# NXPESC-UF1_test004.net
KiCad netlist of a schematic drawn in EAGLE
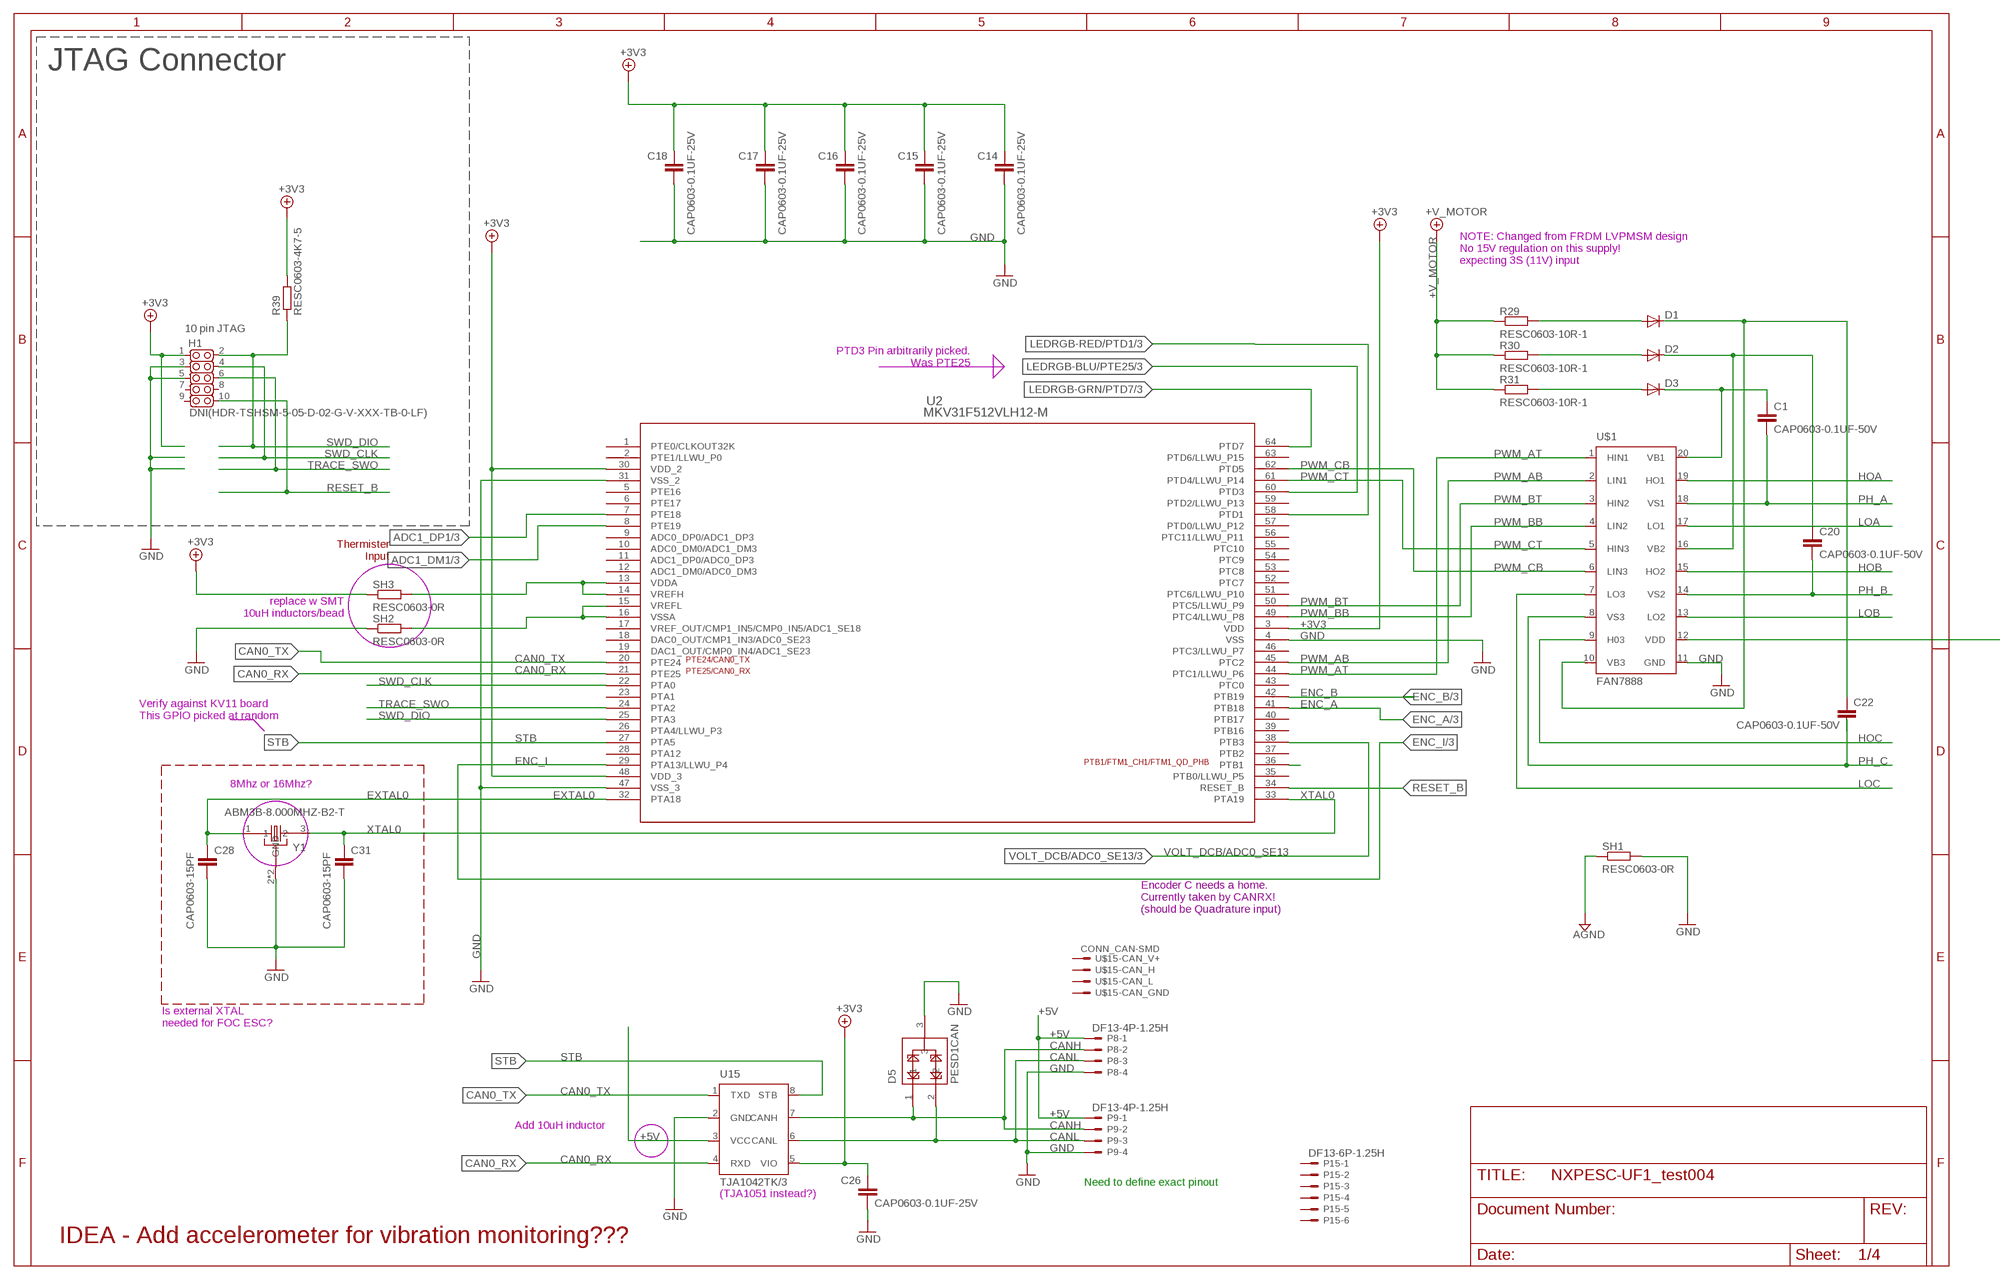
[diagram p0: schematic, sheet 1, part 1 of 2]
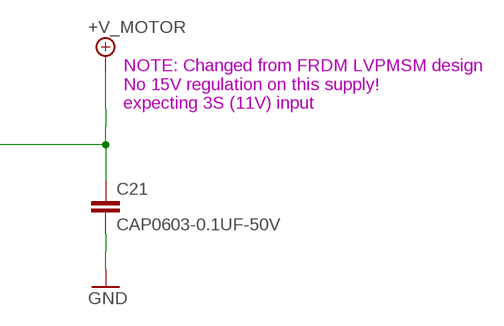
[diagram p1: schematic, sheet 1, part 2 of 2]
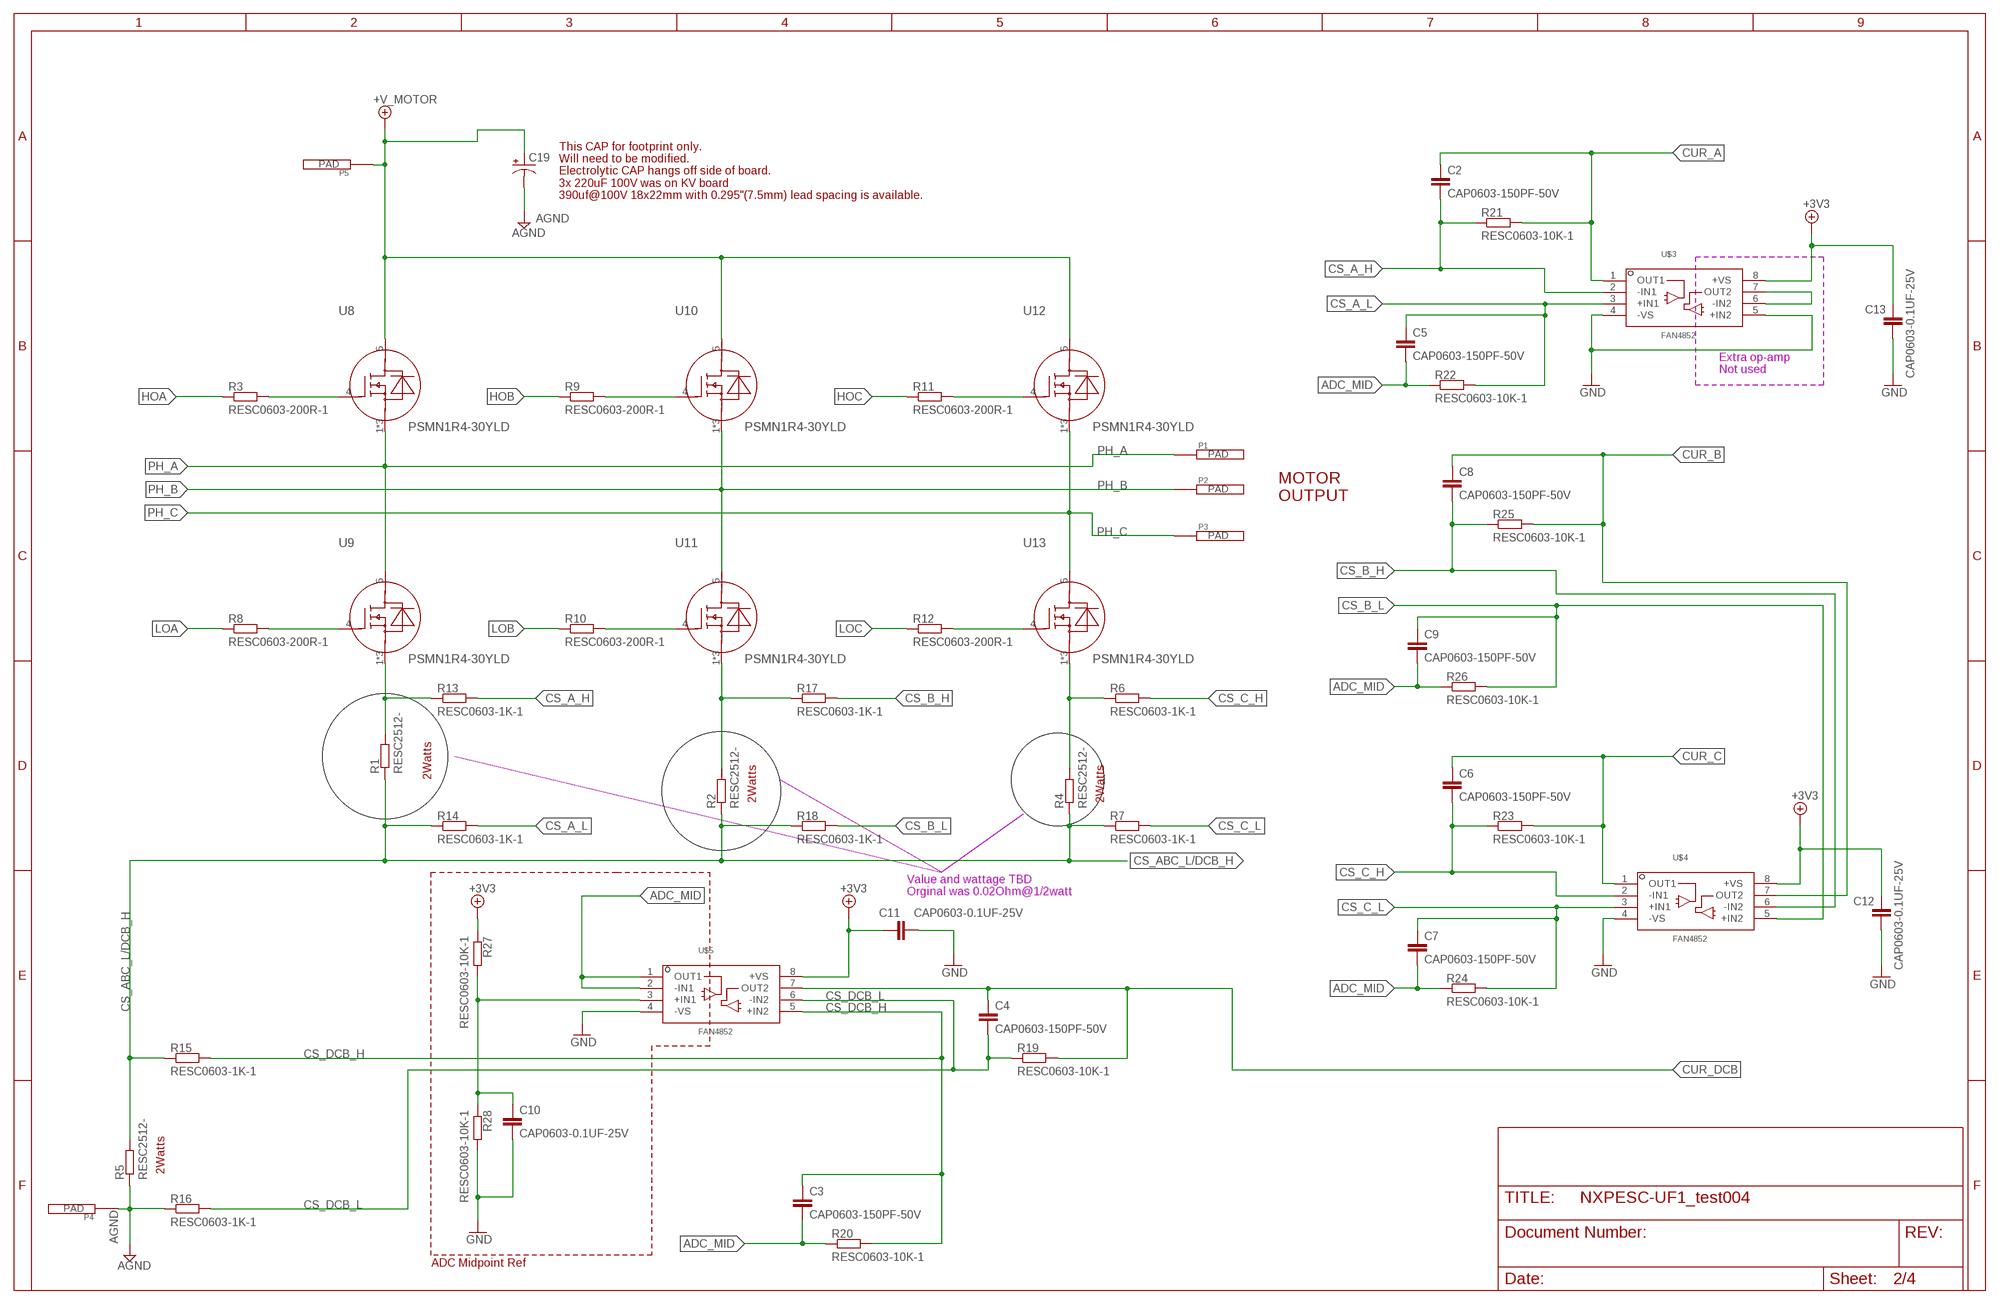
[diagram p2: schematic, sheet 2]
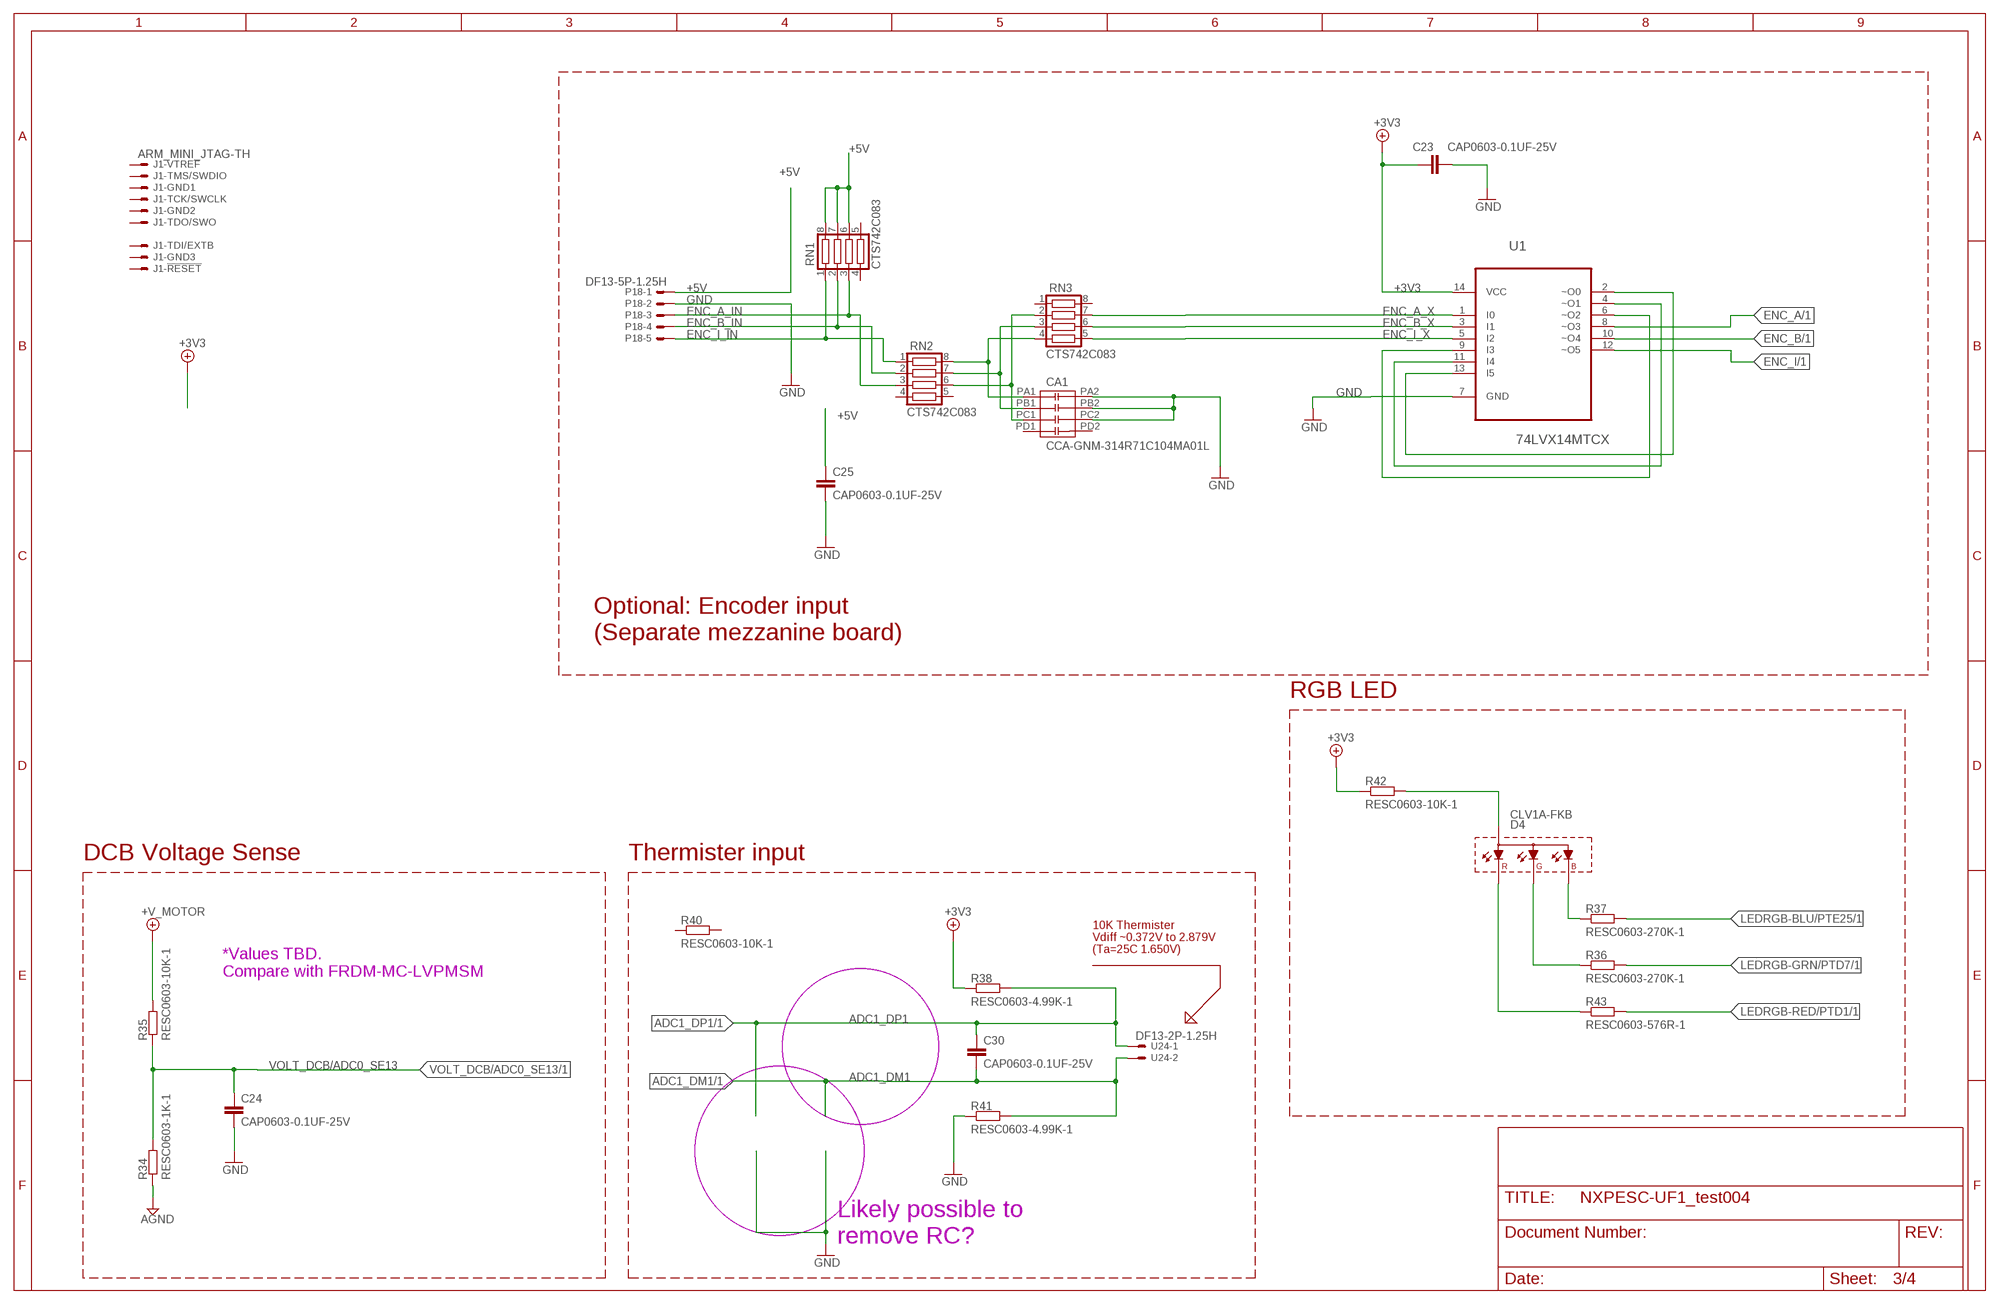
[diagram p3: schematic, sheet 3]

(export (version "E")
  (design (tool "Eeschema 10.0.6"))
  (components
    (comp (ref "C2")
      (value "CAP0603-150PF-50V")
      (footprint "eagle-import:C0603")
      (libsource (lib "eagle-import") (part "CAP?-0603150PF-50V"))
    )
    (comp (ref "C3")
      (value "CAP0603-150PF-50V")
      (footprint "eagle-import:C0603")
      (libsource (lib "eagle-import") (part "CAP?-0603150PF-50V"))
    )
    (comp (ref "C4")
      (value "CAP0603-150PF-50V")
      (footprint "eagle-import:C0603")
      (libsource (lib "eagle-import") (part "CAP?-0603150PF-50V"))
    )
    (comp (ref "C5")
      (value "CAP0603-150PF-50V")
      (footprint "eagle-import:C0603")
      (libsource (lib "eagle-import") (part "CAP?-0603150PF-50V"))
    )
    (comp (ref "C6")
      (value "CAP0603-150PF-50V")
      (footprint "eagle-import:C0603")
      (libsource (lib "eagle-import") (part "CAP?-0603150PF-50V"))
    )
    (comp (ref "C7")
      (value "CAP0603-150PF-50V")
      (footprint "eagle-import:C0603")
      (libsource (lib "eagle-import") (part "CAP?-0603150PF-50V"))
    )
    (comp (ref "C8")
      (value "CAP0603-150PF-50V")
      (footprint "eagle-import:C0603")
      (libsource (lib "eagle-import") (part "CAP?-0603150PF-50V"))
    )
    (comp (ref "C9")
      (value "CAP0603-150PF-50V")
      (footprint "eagle-import:C0603")
      (libsource (lib "eagle-import") (part "CAP?-0603150PF-50V"))
    )
    (comp (ref "C10")
      (value "CAP0603-0.1UF-25V")
      (footprint "eagle-import:C0603")
      (libsource (lib "eagle-import") (part "CAP?-06030.1UF-25V"))
    )
    (comp (ref "C11")
      (value "CAP0603-0.1UF-25V")
      (footprint "eagle-import:C0603")
      (libsource (lib "eagle-import") (part "CAP?-06030.1UF-25V"))
    )
    (comp (ref "C12")
      (value "CAP0603-0.1UF-25V")
      (footprint "eagle-import:C0603")
      (libsource (lib "eagle-import") (part "CAP?-06030.1UF-25V"))
    )
    (comp (ref "C13")
      (value "CAP0603-0.1UF-25V")
      (footprint "eagle-import:C0603")
      (libsource (lib "eagle-import") (part "CAP?-06030.1UF-25V"))
    )
    (comp (ref "C19")
      (value "CPOL-USETR1")
      (footprint "eagle-import:ETR1")
      (libsource (lib "eagle-import") (part "CPOL-USETR1"))
    )
    (comp (ref "P1")
      (value "MOT_PWR_PAD-1")
      (footprint "eagle-import:MPAD1")
      (libsource (lib "eagle-import") (part "MOT_PWR_PAD-1"))
    )
    (comp (ref "P2")
      (value "MOT_PWR_PAD-1")
      (footprint "eagle-import:MPAD1")
      (libsource (lib "eagle-import") (part "MOT_PWR_PAD-1"))
    )
    (comp (ref "P3")
      (value "MOT_PWR_PAD-1")
      (footprint "eagle-import:MPAD1")
      (libsource (lib "eagle-import") (part "MOT_PWR_PAD-1"))
    )
    (comp (ref "P4")
      (value "MOT_PWR_PAD-1")
      (footprint "eagle-import:MPAD1")
      (libsource (lib "eagle-import") (part "MOT_PWR_PAD-1"))
    )
    (comp (ref "P5")
      (value "MOT_PWR_PAD-1")
      (footprint "eagle-import:MPAD1")
      (libsource (lib "eagle-import") (part "MOT_PWR_PAD-1"))
    )
    (comp (ref "R1")
      (value "RESC2512-")
      (footprint "eagle-import:R2512")
      (libsource (lib "eagle-import") (part "RESC?-2512"))
    )
    (comp (ref "R2")
      (value "RESC2512-")
      (footprint "eagle-import:R2512")
      (libsource (lib "eagle-import") (part "RESC?-2512"))
    )
    (comp (ref "R3")
      (value "RESC0603-200R-1")
      (footprint "eagle-import:C0603")
      (libsource (lib "eagle-import") (part "RESC?-0603200R-1"))
    )
    (comp (ref "R4")
      (value "RESC2512-")
      (footprint "eagle-import:R2512")
      (libsource (lib "eagle-import") (part "RESC?-2512"))
    )
    (comp (ref "R5")
      (value "RESC2512-")
      (footprint "eagle-import:R2512")
      (libsource (lib "eagle-import") (part "RESC?-2512"))
    )
    (comp (ref "R6")
      (value "RESC0603-1K-1")
      (footprint "eagle-import:C0603")
      (libsource (lib "eagle-import") (part "RESC?-06031K-1"))
    )
    (comp (ref "R7")
      (value "RESC0603-1K-1")
      (footprint "eagle-import:C0603")
      (libsource (lib "eagle-import") (part "RESC?-06031K-1"))
    )
    (comp (ref "R8")
      (value "RESC0603-200R-1")
      (footprint "eagle-import:C0603")
      (libsource (lib "eagle-import") (part "RESC?-0603200R-1"))
    )
    (comp (ref "R9")
      (value "RESC0603-200R-1")
      (footprint "eagle-import:C0603")
      (libsource (lib "eagle-import") (part "RESC?-0603200R-1"))
    )
    (comp (ref "R10")
      (value "RESC0603-200R-1")
      (footprint "eagle-import:C0603")
      (libsource (lib "eagle-import") (part "RESC?-0603200R-1"))
    )
    (comp (ref "R11")
      (value "RESC0603-200R-1")
      (footprint "eagle-import:C0603")
      (libsource (lib "eagle-import") (part "RESC?-0603200R-1"))
    )
    (comp (ref "R12")
      (value "RESC0603-200R-1")
      (footprint "eagle-import:C0603")
      (libsource (lib "eagle-import") (part "RESC?-0603200R-1"))
    )
    (comp (ref "R13")
      (value "RESC0603-1K-1")
      (footprint "eagle-import:C0603")
      (libsource (lib "eagle-import") (part "RESC?-06031K-1"))
    )
    (comp (ref "R14")
      (value "RESC0603-1K-1")
      (footprint "eagle-import:C0603")
      (libsource (lib "eagle-import") (part "RESC?-06031K-1"))
    )
    (comp (ref "R15")
      (value "RESC0603-1K-1")
      (footprint "eagle-import:C0603")
      (libsource (lib "eagle-import") (part "RESC?-06031K-1"))
    )
    (comp (ref "R16")
      (value "RESC0603-1K-1")
      (footprint "eagle-import:C0603")
      (libsource (lib "eagle-import") (part "RESC?-06031K-1"))
    )
    (comp (ref "R17")
      (value "RESC0603-1K-1")
      (footprint "eagle-import:C0603")
      (libsource (lib "eagle-import") (part "RESC?-06031K-1"))
    )
    (comp (ref "R18")
      (value "RESC0603-1K-1")
      (footprint "eagle-import:C0603")
      (libsource (lib "eagle-import") (part "RESC?-06031K-1"))
    )
    (comp (ref "R19")
      (value "RESC0603-10K-1")
      (footprint "eagle-import:C0603")
      (libsource (lib "eagle-import") (part "RESC?-060310K-1"))
    )
    (comp (ref "R20")
      (value "RESC0603-10K-1")
      (footprint "eagle-import:C0603")
      (libsource (lib "eagle-import") (part "RESC?-060310K-1"))
    )
    (comp (ref "R21")
      (value "RESC0603-10K-1")
      (footprint "eagle-import:C0603")
      (libsource (lib "eagle-import") (part "RESC?-060310K-1"))
    )
    (comp (ref "R22")
      (value "RESC0603-10K-1")
      (footprint "eagle-import:C0603")
      (libsource (lib "eagle-import") (part "RESC?-060310K-1"))
    )
    (comp (ref "R23")
      (value "RESC0603-10K-1")
      (footprint "eagle-import:C0603")
      (libsource (lib "eagle-import") (part "RESC?-060310K-1"))
    )
    (comp (ref "R24")
      (value "RESC0603-10K-1")
      (footprint "eagle-import:C0603")
      (libsource (lib "eagle-import") (part "RESC?-060310K-1"))
    )
    (comp (ref "R25")
      (value "RESC0603-10K-1")
      (footprint "eagle-import:C0603")
      (libsource (lib "eagle-import") (part "RESC?-060310K-1"))
    )
    (comp (ref "R26")
      (value "RESC0603-10K-1")
      (footprint "eagle-import:C0603")
      (libsource (lib "eagle-import") (part "RESC?-060310K-1"))
    )
    (comp (ref "R27")
      (value "RESC0603-10K-1")
      (footprint "eagle-import:C0603")
      (libsource (lib "eagle-import") (part "RESC?-060310K-1"))
    )
    (comp (ref "R28")
      (value "RESC0603-10K-1")
      (footprint "eagle-import:C0603")
      (libsource (lib "eagle-import") (part "RESC?-060310K-1"))
    )
    (comp (ref "U$3")
      (value "FAN4852")
      (footprint "eagle-import:SOP65P490X110-8N")
      (libsource (lib "eagle-import") (part "FAN4852"))
    )
    (comp (ref "U$4")
      (value "FAN4852")
      (footprint "eagle-import:SOP65P490X110-8N")
      (libsource (lib "eagle-import") (part "FAN4852"))
    )
    (comp (ref "U$5")
      (value "FAN4852")
      (footprint "eagle-import:SOP65P490X110-8N")
      (libsource (lib "eagle-import") (part "FAN4852"))
    )
    (comp (ref "U8")
      (value "PSMN1R4-30YLD")
      (footprint "eagle-import:LFPAK56")
      (libsource (lib "eagle-import") (part "PSMN1R4-30YLD"))
    )
    (comp (ref "U9")
      (value "PSMN1R4-30YLD")
      (footprint "eagle-import:LFPAK56")
      (libsource (lib "eagle-import") (part "PSMN1R4-30YLD"))
    )
    (comp (ref "U10")
      (value "PSMN1R4-30YLD")
      (footprint "eagle-import:LFPAK56")
      (libsource (lib "eagle-import") (part "PSMN1R4-30YLD"))
    )
    (comp (ref "U11")
      (value "PSMN1R4-30YLD")
      (footprint "eagle-import:LFPAK56")
      (libsource (lib "eagle-import") (part "PSMN1R4-30YLD"))
    )
    (comp (ref "U12")
      (value "PSMN1R4-30YLD")
      (footprint "eagle-import:LFPAK56")
      (libsource (lib "eagle-import") (part "PSMN1R4-30YLD"))
    )
    (comp (ref "U13")
      (value "PSMN1R4-30YLD")
      (footprint "eagle-import:LFPAK56")
      (libsource (lib "eagle-import") (part "PSMN1R4-30YLD"))
    )
    (comp (ref "C1")
      (value "CAP0603-0.1UF-50V")
      (footprint "eagle-import:C0603")
      (libsource (lib "eagle-import") (part "CAP?-06030.1UF-50V"))
    )
    (comp (ref "C14")
      (value "CAP0603-0.1UF-25V")
      (footprint "eagle-import:C0603")
      (libsource (lib "eagle-import") (part "CAP?-06030.1UF-25V"))
    )
    (comp (ref "C15")
      (value "CAP0603-0.1UF-25V")
      (footprint "eagle-import:C0603")
      (libsource (lib "eagle-import") (part "CAP?-06030.1UF-25V"))
    )
    (comp (ref "C16")
      (value "CAP0603-0.1UF-25V")
      (footprint "eagle-import:C0603")
      (libsource (lib "eagle-import") (part "CAP?-06030.1UF-25V"))
    )
    (comp (ref "C17")
      (value "CAP0603-0.1UF-25V")
      (footprint "eagle-import:C0603")
      (libsource (lib "eagle-import") (part "CAP?-06030.1UF-25V"))
    )
    (comp (ref "C18")
      (value "CAP0603-0.1UF-25V")
      (footprint "eagle-import:C0603")
      (libsource (lib "eagle-import") (part "CAP?-06030.1UF-25V"))
    )
    (comp (ref "C20")
      (value "CAP0603-0.1UF-50V")
      (footprint "eagle-import:C0603")
      (libsource (lib "eagle-import") (part "CAP?-06030.1UF-50V"))
    )
    (comp (ref "C21")
      (value "CAP0603-0.1UF-50V")
      (footprint "eagle-import:C0603")
      (libsource (lib "eagle-import") (part "CAP?-06030.1UF-50V"))
    )
    (comp (ref "C22")
      (value "CAP0603-0.1UF-50V")
      (footprint "eagle-import:C0603")
      (libsource (lib "eagle-import") (part "CAP?-06030.1UF-50V"))
    )
    (comp (ref "C26")
      (value "CAP0603-0.1UF-25V")
      (footprint "eagle-import:C0603")
      (libsource (lib "eagle-import") (part "CAP?-06030.1UF-25V"))
    )
    (comp (ref "C28")
      (value "CAP0603-15PF")
      (footprint "eagle-import:C0603")
      (libsource (lib "eagle-import") (part "CAP?-060315PF"))
    )
    (comp (ref "C31")
      (value "CAP0603-15PF")
      (footprint "eagle-import:C0603")
      (libsource (lib "eagle-import") (part "CAP?-060315PF"))
    )
    (comp (ref "D1")
      (value "DIODE-SOD323-R")
      (footprint "eagle-import:SOD323-R")
      (libsource (lib "eagle-import") (part "DIODE-SOD323-R"))
    )
    (comp (ref "D2")
      (value "DIODE-SOD323-R")
      (footprint "eagle-import:SOD323-R")
      (libsource (lib "eagle-import") (part "DIODE-SOD323-R"))
    )
    (comp (ref "D3")
      (value "DIODE-SOD323-R")
      (footprint "eagle-import:SOD323-R")
      (libsource (lib "eagle-import") (part "DIODE-SOD323-R"))
    )
    (comp (ref "D5")
      (value "PESD1CAN")
      (footprint "eagle-import:SOT23-3")
      (libsource (lib "eagle-import") (part "PESD1CAN"))
    )
    (comp (ref "H1")
      (value "DNI(HDR-TSHSM-5-05-D-02-G-V-XXX-TB-0-LF)")
      (footprint "eagle-import:HD2X5-SMD-0.05_")
      (libsource (lib "eagle-import") (part "HDR-TSHSM-5--D-02-G-V-XXX-TB-0-LF05"))
    )
    (comp (ref "P8")
      (value "DF13-4P-1.25H")
      (footprint "eagle-import:DF13A-4P-1.25H")
      (libsource (lib "eagle-import") (part "DF13-4P-1.25?H"))
    )
    (comp (ref "P9")
      (value "DF13-4P-1.25H")
      (footprint "eagle-import:DF13A-4P-1.25H")
      (libsource (lib "eagle-import") (part "DF13-4P-1.25?H"))
    )
    (comp (ref "P15")
      (value "DF13-6P-1.25H")
      (footprint "eagle-import:DF13A-6P-1.25H")
      (libsource (lib "eagle-import") (part "DF13-6P-1.25?H"))
    )
    (comp (ref "R29")
      (value "RESC0603-10R-1")
      (footprint "eagle-import:C0603")
      (libsource (lib "eagle-import") (part "RESC?-060310R-1"))
    )
    (comp (ref "R30")
      (value "RESC0603-10R-1")
      (footprint "eagle-import:C0603")
      (libsource (lib "eagle-import") (part "RESC?-060310R-1"))
    )
    (comp (ref "R31")
      (value "RESC0603-10R-1")
      (footprint "eagle-import:C0603")
      (libsource (lib "eagle-import") (part "RESC?-060310R-1"))
    )
    (comp (ref "R39")
      (value "RESC0603-4K7-5")
      (footprint "eagle-import:C0603")
      (libsource (lib "eagle-import") (part "etc_rcl_RESC?-06034K7-5"))
    )
    (comp (ref "SH1")
      (value "RESC0603-0R")
      (footprint "eagle-import:C0603")
      (libsource (lib "eagle-import") (part "RESC?-06030R"))
    )
    (comp (ref "SH2")
      (value "RESC0603-0R")
      (footprint "eagle-import:C0603")
      (libsource (lib "eagle-import") (part "RESC?-06030R"))
    )
    (comp (ref "SH3")
      (value "RESC0603-0R")
      (footprint "eagle-import:C0603")
      (libsource (lib "eagle-import") (part "RESC?-06030R"))
    )
    (comp (ref "U$1")
      (value "FAN7888")
      (footprint "eagle-import:SOIC-20")
      (libsource (lib "eagle-import") (part "FAN7888"))
    )
    (comp (ref "U$15")
      (value "CONN_CAN-SMD")
      (footprint "eagle-import:S4B-PH-SM4-TB")
      (libsource (lib "eagle-import") (part "CONN_CAN-SMD"))
    )
    (comp (ref "U2")
      (value "MKV31F512VLH12-M")
      (footprint "eagle-import:LQFP-64_10X10X1_6-M")
      (libsource (lib "eagle-import") (part "MKV31F512VLH12-M"))
    )
    (comp (ref "U15")
      (value "TJA1042TK/3")
      (footprint "eagle-import:HVSON8")
      (libsource (lib "eagle-import") (part "TJA1042TK/3"))
    )
    (comp (ref "Y1")
      (value "ABM3B-8.000MHZ-B2-T")
      (footprint "eagle-import:OSCSC500X320X110-4N")
      (libsource (lib "eagle-import") (part "ABM3B-8.000MHZ-B2-T"))
    )
    (comp (ref "C23")
      (value "CAP0603-0.1UF-25V")
      (footprint "eagle-import:C0603")
      (libsource (lib "eagle-import") (part "CAP?-06030.1UF-25V"))
    )
    (comp (ref "C24")
      (value "CAP0603-0.1UF-25V")
      (footprint "eagle-import:C0603")
      (libsource (lib "eagle-import") (part "CAP?-06030.1UF-25V"))
    )
    (comp (ref "C25")
      (value "CAP0603-0.1UF-25V")
      (footprint "eagle-import:C0603")
      (libsource (lib "eagle-import") (part "CAP?-06030.1UF-25V"))
    )
    (comp (ref "C30")
      (value "CAP0603-0.1UF-25V")
      (footprint "eagle-import:C0603")
      (libsource (lib "eagle-import") (part "CAP?-06030.1UF-25V"))
    )
    (comp (ref "CA1")
      (value "CCA-GNM-314R71C104MA01L")
      (footprint "eagle-import:RES_ARRAY_4I_S")
      (libsource (lib "eagle-import") (part "CCA-?-GNM314R71C104MA01L"))
    )
    (comp (ref "D4")
      (value "CLV1A-FKB")
      (footprint "eagle-import:4-PLCC")
      (libsource (lib "eagle-import") (part "CLV1A-FKB"))
    )
    (comp (ref "J1")
      (value "ARM_MINI_JTAG-TH")
      (footprint "eagle-import:FTSH-105-01-XXX-DV")
      (libsource (lib "eagle-import") (part "ARM_MINI_JTAG-TH"))
    )
    (comp (ref "P18")
      (value "DF13-5P-1.25H")
      (footprint "eagle-import:DF13A-5P-1.25H")
      (libsource (lib "eagle-import") (part "DF13-5P-1.25?H"))
    )
    (comp (ref "R34")
      (value "RESC0603-1K-1")
      (footprint "eagle-import:C0603")
      (libsource (lib "eagle-import") (part "RESC?-06031K-1"))
    )
    (comp (ref "R35")
      (value "RESC0603-10K-1")
      (footprint "eagle-import:C0603")
      (libsource (lib "eagle-import") (part "RESC?-060310K-1"))
    )
    (comp (ref "R36")
      (value "RESC0603-270K-1")
      (footprint "eagle-import:C0603")
      (libsource (lib "eagle-import") (part "RESC?-0603270K-1"))
    )
    (comp (ref "R37")
      (value "RESC0603-270K-1")
      (footprint "eagle-import:C0603")
      (libsource (lib "eagle-import") (part "RESC?-0603270K-1"))
    )
    (comp (ref "R38")
      (value "RESC0603-4.99K-1")
      (footprint "eagle-import:C0603")
      (libsource (lib "eagle-import") (part "RESC?-06034.99K-1"))
    )
    (comp (ref "R40")
      (value "RESC0603-10K-1")
      (footprint "eagle-import:C0603")
      (libsource (lib "eagle-import") (part "RESC?-060310K-1"))
    )
    (comp (ref "R41")
      (value "RESC0603-4.99K-1")
      (footprint "eagle-import:C0603")
      (libsource (lib "eagle-import") (part "RESC?-06034.99K-1"))
    )
    (comp (ref "R42")
      (value "RESC0603-10K-1")
      (footprint "eagle-import:C0603")
      (libsource (lib "eagle-import") (part "RESC?-060310K-1"))
    )
    (comp (ref "R43")
      (value "RESC0603-576R-1")
      (footprint "eagle-import:C0603")
      (libsource (lib "eagle-import") (part "RESC?-0603576R-1"))
    )
    (comp (ref "RN1")
      (value "CTS742C083")
      (footprint "eagle-import:CTS742C083")
      (libsource (lib "eagle-import") (part "CTS742C083"))
    )
    (comp (ref "RN2")
      (value "CTS742C083")
      (footprint "eagle-import:CTS742C083")
      (libsource (lib "eagle-import") (part "CTS742C083"))
    )
    (comp (ref "RN3")
      (value "CTS742C083")
      (footprint "eagle-import:CTS742C083")
      (libsource (lib "eagle-import") (part "CTS742C083"))
    )
    (comp (ref "U1")
      (value "74LVX14MTCX")
      (footprint "eagle-import:SOP65P640X120-14N")
      (libsource (lib "eagle-import") (part "74LVX14MTCX"))
    )
    (comp (ref "U24")
      (value "DF13-2P-1.25H")
      (footprint "eagle-import:DF13A-2P-1.25H")
      (libsource (lib "eagle-import") (part "DF13-2P-1.25?H"))
    )
  )
  (nets
    (net (code "1") (name "+3V3") (class "Default")
      (node (ref "C11") (pin "1") (pinfunction "1_1") (pintype "passive"))
      (node (ref "C12") (pin "1") (pinfunction "1_1") (pintype "passive"))
      (node (ref "C13") (pin "1") (pinfunction "1_1") (pintype "passive"))
      (node (ref "C14") (pin "1") (pinfunction "1_1") (pintype "passive"))
      (node (ref "C15") (pin "1") (pinfunction "1_1") (pintype "passive"))
      (node (ref "C16") (pin "1") (pinfunction "1_1") (pintype "passive"))
      (node (ref "C17") (pin "1") (pinfunction "1_1") (pintype "passive"))
      (node (ref "C18") (pin "1") (pinfunction "1_1") (pintype "passive"))
      (node (ref "C23") (pin "1") (pinfunction "1_1") (pintype "passive"))
      (node (ref "C26") (pin "1") (pinfunction "1_1") (pintype "passive"))
      (node (ref "H1") (pin "1") (pinfunction "1_1") (pintype "passive"))
      (node (ref "R27") (pin "1") (pinfunction "1_1") (pintype "passive"))
      (node (ref "R38") (pin "1") (pinfunction "1_1") (pintype "passive"))
      (node (ref "R39") (pin "2") (pinfunction "2_2") (pintype "passive"))
      (node (ref "R42") (pin "1") (pinfunction "1_1") (pintype "passive"))
      (node (ref "SH3") (pin "1") (pinfunction "1_1") (pintype "passive"))
      (node (ref "U$3") (pin "8") (pinfunction "+VS_8") (pintype "passive"))
      (node (ref "U$4") (pin "8") (pinfunction "+VS_8") (pintype "passive"))
      (node (ref "U$5") (pin "8") (pinfunction "+VS_8") (pintype "passive"))
      (node (ref "U1") (pin "14") (pinfunction "VCC_14") (pintype "power_in"))
      (node (ref "U15") (pin "5") (pinfunction "VIO_5") (pintype "power_in"))
      (node (ref "U2") (pin "3") (pinfunction "VDD_3") (pintype "power_in"))
      (node (ref "U2") (pin "30") (pinfunction "VDD_2_30") (pintype "power_in"))
      (node (ref "U2") (pin "48") (pinfunction "VDD_3_48") (pintype "power_in"))
    )
    (net (code "2") (name "+5V") (class "Default")
      (node (ref "C25") (pin "1") (pinfunction "1_1") (pintype "passive"))
      (node (ref "P18") (pin "1") (pinfunction "S_1") (pintype "passive"))
      (node (ref "P8") (pin "1") (pinfunction "S_1") (pintype "passive"))
      (node (ref "P9") (pin "1") (pinfunction "S_1") (pintype "passive"))
      (node (ref "RN1") (pin "6") (pinfunction "6_6") (pintype "passive"))
      (node (ref "RN1") (pin "7") (pinfunction "7_7") (pintype "passive"))
      (node (ref "RN1") (pin "8") (pinfunction "8_8") (pintype "passive"))
      (node (ref "U15") (pin "3") (pinfunction "VCC_3") (pintype "power_in"))
    )
    (net (code "3") (name "+V_MOTOR") (class "Default")
      (node (ref "C19") (pin "+") (pinfunction "+_+") (pintype "passive"))
      (node (ref "C21") (pin "1") (pinfunction "1_1") (pintype "passive"))
      (node (ref "P5") (pin "P$1") (pinfunction "PAD_P$1") (pintype "passive"))
      (node (ref "R29") (pin "1") (pinfunction "1_1") (pintype "passive"))
      (node (ref "R30") (pin "1") (pinfunction "1_1") (pintype "passive"))
      (node (ref "R31") (pin "1") (pinfunction "1_1") (pintype "passive"))
      (node (ref "R35") (pin "2") (pinfunction "2_2") (pintype "passive"))
      (node (ref "U$1") (pin "12") (pinfunction "VDD_12") (pintype "power_in"))
      (node (ref "U10") (pin "5") (pinfunction "D_5") (pintype "open_collector"))
      (node (ref "U12") (pin "5") (pinfunction "D_5") (pintype "open_collector"))
      (node (ref "U8") (pin "5") (pinfunction "D_5") (pintype "open_collector"))
    )
    (net (code "4") (name "ADC1_DM1") (class "Default")
      (node (ref "C30") (pin "2") (pinfunction "2_2") (pintype "passive"))
      (node (ref "R41") (pin "2") (pinfunction "2_2") (pintype "passive"))
      (node (ref "U2") (pin "8") (pinfunction "PTE19_8") (pintype "bidirectional"))
      (node (ref "U24") (pin "2") (pinfunction "S_2") (pintype "passive"))
    )
    (net (code "5") (name "ADC1_DP1") (class "Default")
      (node (ref "C30") (pin "1") (pinfunction "1_1") (pintype "passive"))
      (node (ref "R38") (pin "2") (pinfunction "2_2") (pintype "passive"))
      (node (ref "U2") (pin "7") (pinfunction "PTE18_7") (pintype "bidirectional"))
      (node (ref "U24") (pin "1") (pinfunction "S_1") (pintype "passive"))
    )
    (net (code "6") (name "ADC_MID") (class "Default")
      (node (ref "C3") (pin "2") (pinfunction "2_2") (pintype "passive"))
      (node (ref "C5") (pin "2") (pinfunction "2_2") (pintype "passive"))
      (node (ref "C7") (pin "2") (pinfunction "2_2") (pintype "passive"))
      (node (ref "C9") (pin "2") (pinfunction "2_2") (pintype "passive"))
      (node (ref "R20") (pin "1") (pinfunction "1_1") (pintype "passive"))
      (node (ref "R22") (pin "1") (pinfunction "1_1") (pintype "passive"))
      (node (ref "R24") (pin "1") (pinfunction "1_1") (pintype "passive"))
      (node (ref "R26") (pin "1") (pinfunction "1_1") (pintype "passive"))
      (node (ref "U$5") (pin "1") (pinfunction "OUT1_1") (pintype "output"))
      (node (ref "U$5") (pin "2") (pinfunction "-IN1_2") (pintype "input"))
    )
    (net (code "7") (name "AGND") (class "Default")
      (node (ref "C19") (pin "-") (pinfunction "-_-") (pintype "passive"))
      (node (ref "P4") (pin "P$1") (pinfunction "PAD_P$1") (pintype "passive"))
      (node (ref "R16") (pin "1") (pinfunction "1_1") (pintype "passive"))
      (node (ref "R34") (pin "1") (pinfunction "1_1") (pintype "passive"))
      (node (ref "R5") (pin "1") (pinfunction "1_1") (pintype "passive"))
      (node (ref "SH1") (pin "1") (pinfunction "1_1") (pintype "passive"))
    )
    (net (code "8") (name "CAN0_RX") (class "Default")
      (node (ref "U15") (pin "4") (pinfunction "RXD_4") (pintype "output"))
      (node (ref "U2") (pin "21") (pinfunction "PTE25_21") (pintype "bidirectional"))
    )
    (net (code "9") (name "CAN0_TX") (class "Default")
      (node (ref "U15") (pin "1") (pinfunction "TXD_1") (pintype "input"))
      (node (ref "U2") (pin "20") (pinfunction "PTE24_20") (pintype "bidirectional"))
    )
    (net (code "10") (name "CANH") (class "Default")
      (node (ref "D5") (pin "1") (pinfunction "1_1") (pintype "bidirectional"))
      (node (ref "P8") (pin "2") (pinfunction "S_2") (pintype "passive"))
      (node (ref "P9") (pin "2") (pinfunction "S_2") (pintype "passive"))
      (node (ref "U15") (pin "7") (pinfunction "CANH_7") (pintype "output"))
    )
    (net (code "11") (name "CANL") (class "Default")
      (node (ref "D5") (pin "2") (pinfunction "2_2") (pintype "bidirectional"))
      (node (ref "P8") (pin "3") (pinfunction "S_3") (pintype "passive"))
      (node (ref "P9") (pin "3") (pinfunction "S_3") (pintype "passive"))
      (node (ref "U15") (pin "6") (pinfunction "CANL_6") (pintype "output"))
    )
    (net (code "12") (name "CS_ABC_L{slash}DCB_H") (class "Default")
      (node (ref "R1") (pin "1") (pinfunction "1_1") (pintype "passive"))
      (node (ref "R14") (pin "1") (pinfunction "1_1") (pintype "passive"))
      (node (ref "R15") (pin "1") (pinfunction "1_1") (pintype "passive"))
      (node (ref "R18") (pin "1") (pinfunction "1_1") (pintype "passive"))
      (node (ref "R2") (pin "1") (pinfunction "1_1") (pintype "passive"))
      (node (ref "R4") (pin "1") (pinfunction "1_1") (pintype "passive"))
      (node (ref "R5") (pin "2") (pinfunction "2_2") (pintype "passive"))
      (node (ref "R7") (pin "1") (pinfunction "1_1") (pintype "passive"))
    )
    (net (code "13") (name "CS_A_H") (class "Default")
      (node (ref "C2") (pin "2") (pinfunction "2_2") (pintype "passive"))
      (node (ref "R13") (pin "2") (pinfunction "2_2") (pintype "passive"))
      (node (ref "R21") (pin "1") (pinfunction "1_1") (pintype "passive"))
      (node (ref "U$3") (pin "2") (pinfunction "-IN1_2") (pintype "input"))
    )
    (net (code "14") (name "CS_A_L") (class "Default")
      (node (ref "C5") (pin "1") (pinfunction "1_1") (pintype "passive"))
      (node (ref "R14") (pin "2") (pinfunction "2_2") (pintype "passive"))
      (node (ref "R22") (pin "2") (pinfunction "2_2") (pintype "passive"))
      (node (ref "U$3") (pin "3") (pinfunction "+IN1_3") (pintype "input"))
    )
    (net (code "15") (name "CS_B_H") (class "Default")
      (node (ref "C8") (pin "2") (pinfunction "2_2") (pintype "passive"))
      (node (ref "R17") (pin "2") (pinfunction "2_2") (pintype "passive"))
      (node (ref "R25") (pin "1") (pinfunction "1_1") (pintype "passive"))
      (node (ref "U$4") (pin "6") (pinfunction "-IN2_6") (pintype "input"))
    )
    (net (code "16") (name "CS_B_L") (class "Default")
      (node (ref "C9") (pin "1") (pinfunction "1_1") (pintype "passive"))
      (node (ref "R18") (pin "2") (pinfunction "2_2") (pintype "passive"))
      (node (ref "R26") (pin "2") (pinfunction "2_2") (pintype "passive"))
      (node (ref "U$4") (pin "5") (pinfunction "+IN2_5") (pintype "input"))
    )
    (net (code "17") (name "CS_C_H") (class "Default")
      (node (ref "C6") (pin "2") (pinfunction "2_2") (pintype "passive"))
      (node (ref "R23") (pin "1") (pinfunction "1_1") (pintype "passive"))
      (node (ref "R6") (pin "2") (pinfunction "2_2") (pintype "passive"))
      (node (ref "U$4") (pin "2") (pinfunction "-IN1_2") (pintype "input"))
    )
    (net (code "18") (name "CS_C_L") (class "Default")
      (node (ref "C7") (pin "1") (pinfunction "1_1") (pintype "passive"))
      (node (ref "R24") (pin "2") (pinfunction "2_2") (pintype "passive"))
      (node (ref "R7") (pin "2") (pinfunction "2_2") (pintype "passive"))
      (node (ref "U$4") (pin "3") (pinfunction "+IN1_3") (pintype "input"))
    )
    (net (code "19") (name "CS_DCB_H") (class "Default")
      (node (ref "C3") (pin "1") (pinfunction "1_1") (pintype "passive"))
      (node (ref "R15") (pin "2") (pinfunction "2_2") (pintype "passive"))
      (node (ref "R20") (pin "2") (pinfunction "2_2") (pintype "passive"))
      (node (ref "U$5") (pin "5") (pinfunction "+IN2_5") (pintype "input"))
    )
    (net (code "20") (name "CS_DCB_L") (class "Default")
      (node (ref "C4") (pin "2") (pinfunction "2_2") (pintype "passive"))
      (node (ref "R16") (pin "2") (pinfunction "2_2") (pintype "passive"))
      (node (ref "R19") (pin "1") (pinfunction "1_1") (pintype "passive"))
      (node (ref "U$5") (pin "6") (pinfunction "-IN2_6") (pintype "input"))
    )
    (net (code "21") (name "CUR_A") (class "Default")
      (node (ref "C2") (pin "1") (pinfunction "1_1") (pintype "passive"))
      (node (ref "R21") (pin "2") (pinfunction "2_2") (pintype "passive"))
      (node (ref "U$3") (pin "1") (pinfunction "OUT1_1") (pintype "output"))
    )
    (net (code "22") (name "CUR_B") (class "Default")
      (node (ref "C8") (pin "1") (pinfunction "1_1") (pintype "passive"))
      (node (ref "R25") (pin "2") (pinfunction "2_2") (pintype "passive"))
      (node (ref "U$4") (pin "7") (pinfunction "OUT2_7") (pintype "output"))
    )
    (net (code "23") (name "CUR_C") (class "Default")
      (node (ref "C6") (pin "1") (pinfunction "1_1") (pintype "passive"))
      (node (ref "R23") (pin "2") (pinfunction "2_2") (pintype "passive"))
      (node (ref "U$4") (pin "1") (pinfunction "OUT1_1") (pintype "output"))
    )
    (net (code "24") (name "CUR_DCB") (class "Default")
      (node (ref "C4") (pin "1") (pinfunction "1_1") (pintype "passive"))
      (node (ref "R19") (pin "2") (pinfunction "2_2") (pintype "passive"))
      (node (ref "U$5") (pin "7") (pinfunction "OUT2_7") (pintype "output"))
    )
    (net (code "25") (name "ENC_A") (class "Default")
      (node (ref "U1") (pin "8") (pinfunction "~{O3}_8") (pintype "output"))
      (node (ref "U2") (pin "41") (pinfunction "PTB18_41") (pintype "bidirectional"))
    )
    (net (code "26") (name "ENC_A_IN") (class "Default")
      (node (ref "P18") (pin "3") (pinfunction "S_3") (pintype "passive"))
      (node (ref "RN1") (pin "3") (pinfunction "3_3") (pintype "passive"))
      (node (ref "RN2") (pin "3") (pinfunction "3_3") (pintype "passive"))
    )
    (net (code "27") (name "ENC_A_X") (class "Default")
      (node (ref "RN3") (pin "7") (pinfunction "7_7") (pintype "passive"))
      (node (ref "U1") (pin "1") (pinfunction "I0_1") (pintype "input"))
    )
    (net (code "28") (name "ENC_B") (class "Default")
      (node (ref "U1") (pin "10") (pinfunction "~{O4}_10") (pintype "output"))
      (node (ref "U2") (pin "42") (pinfunction "PTB19_42") (pintype "bidirectional"))
    )
    (net (code "29") (name "ENC_B_IN") (class "Default")
      (node (ref "P18") (pin "4") (pinfunction "S_4") (pintype "passive"))
      (node (ref "RN1") (pin "2") (pinfunction "2_2") (pintype "passive"))
      (node (ref "RN2") (pin "2") (pinfunction "2_2") (pintype "passive"))
    )
    (net (code "30") (name "ENC_B_X") (class "Default")
      (node (ref "RN3") (pin "6") (pinfunction "6_6") (pintype "passive"))
      (node (ref "U1") (pin "3") (pinfunction "I1_3") (pintype "input"))
    )
    (net (code "31") (name "ENC_I") (class "Default")
      (node (ref "U1") (pin "12") (pinfunction "~{O5}_12") (pintype "output"))
      (node (ref "U2") (pin "29") (pinfunction "PTA13/LLWU_P4_29") (pintype "bidirectional"))
    )
    (net (code "32") (name "ENC_I_IN") (class "Default")
      (node (ref "P18") (pin "5") (pinfunction "S_5") (pintype "passive"))
      (node (ref "RN1") (pin "1") (pinfunction "1_1") (pintype "passive"))
      (node (ref "RN2") (pin "1") (pinfunction "1_1") (pintype "passive"))
    )
    (net (code "33") (name "ENC_I_X") (class "Default")
      (node (ref "RN3") (pin "5") (pinfunction "5_5") (pintype "passive"))
      (node (ref "U1") (pin "5") (pinfunction "I2_5") (pintype "input"))
    )
    (net (code "34") (name "EXTAL0") (class "Default")
      (node (ref "C28") (pin "1") (pinfunction "1_1") (pintype "passive"))
      (node (ref "U2") (pin "32") (pinfunction "PTA18_32") (pintype "bidirectional"))
      (node (ref "Y1") (pin "1") (pinfunction "1_1") (pintype "passive"))
    )
    (net (code "35") (name "GND") (class "Default")
      (node (ref "C10") (pin "2") (pinfunction "2_2") (pintype "passive"))
      (node (ref "C11") (pin "2") (pinfunction "2_2") (pintype "passive"))
      (node (ref "C12") (pin "2") (pinfunction "2_2") (pintype "passive"))
      (node (ref "C13") (pin "2") (pinfunction "2_2") (pintype "passive"))
      (node (ref "C14") (pin "2") (pinfunction "2_2") (pintype "passive"))
      (node (ref "C15") (pin "2") (pinfunction "2_2") (pintype "passive"))
      (node (ref "C16") (pin "2") (pinfunction "2_2") (pintype "passive"))
      (node (ref "C17") (pin "2") (pinfunction "2_2") (pintype "passive"))
      (node (ref "C18") (pin "2") (pinfunction "2_2") (pintype "passive"))
      (node (ref "C21") (pin "2") (pinfunction "2_2") (pintype "passive"))
      (node (ref "C23") (pin "2") (pinfunction "2_2") (pintype "passive"))
      (node (ref "C24") (pin "2") (pinfunction "2_2") (pintype "passive"))
      (node (ref "C25") (pin "2") (pinfunction "2_2") (pintype "passive"))
      (node (ref "C26") (pin "2") (pinfunction "2_2") (pintype "passive"))
      (node (ref "C28") (pin "2") (pinfunction "2_2") (pintype "passive"))
      (node (ref "C31") (pin "2") (pinfunction "2_2") (pintype "passive"))
      (node (ref "CA1") (pin "PA2") (pinfunction "RA2_PA2") (pintype "passive"))
      (node (ref "CA1") (pin "PB2") (pinfunction "RB2_PB2") (pintype "passive"))
      (node (ref "CA1") (pin "PC2") (pinfunction "RC2_PC2") (pintype "passive"))
      (node (ref "D5") (pin "3") (pinfunction "3_3") (pintype "bidirectional"))
      (node (ref "H1") (pin "3") (pinfunction "3_3") (pintype "passive"))
      (node (ref "H1") (pin "5") (pinfunction "5_5") (pintype "passive"))
      (node (ref "P18") (pin "2") (pinfunction "S_2") (pintype "passive"))
      (node (ref "P8") (pin "4") (pinfunction "S_4") (pintype "passive"))
      (node (ref "P9") (pin "4") (pinfunction "S_4") (pintype "passive"))
      (node (ref "R28") (pin "2") (pinfunction "2_2") (pintype "passive"))
      (node (ref "R41") (pin "1") (pinfunction "1_1") (pintype "passive"))
      (node (ref "SH1") (pin "2") (pinfunction "2_2") (pintype "passive"))
      (node (ref "SH2") (pin "1") (pinfunction "1_1") (pintype "passive"))
      (node (ref "U$1") (pin "11") (pinfunction "GND_11") (pintype "passive"))
      (node (ref "U$3") (pin "4") (pinfunction "-VS_4") (pintype "passive"))
      (node (ref "U$3") (pin "5") (pinfunction "+IN2_5") (pintype "input"))
      (node (ref "U$4") (pin "4") (pinfunction "-VS_4") (pintype "passive"))
      (node (ref "U$5") (pin "4") (pinfunction "-VS_4") (pintype "passive"))
      (node (ref "U1") (pin "7") (pinfunction "GND_7") (pintype "passive"))
      (node (ref "U15") (pin "2") (pinfunction "GND_2") (pintype "passive"))
      (node (ref "U2") (pin "31") (pinfunction "VSS_2_31") (pintype "power_in"))
      (node (ref "U2") (pin "4") (pinfunction "VSS_4") (pintype "power_in"))
      (node (ref "U2") (pin "47") (pinfunction "VSS_3_47") (pintype "power_in"))
      (node (ref "Y1") (pin "2") (pinfunction "GND_2") (pintype "passive"))
      (node (ref "Y1") (pin "4") (pinfunction "GND_4") (pintype "passive"))
    )
    (net (code "36") (name "HOA") (class "Default")
      (node (ref "R3") (pin "1") (pinfunction "1_1") (pintype "passive"))
      (node (ref "U$1") (pin "19") (pinfunction "HO1_19") (pintype "output"))
    )
    (net (code "37") (name "HOB") (class "Default")
      (node (ref "R9") (pin "1") (pinfunction "1_1") (pintype "passive"))
      (node (ref "U$1") (pin "15") (pinfunction "HO2_15") (pintype "output"))
    )
    (net (code "38") (name "HOC") (class "Default")
      (node (ref "R11") (pin "1") (pinfunction "1_1") (pintype "passive"))
      (node (ref "U$1") (pin "9") (pinfunction "H03_9") (pintype "output"))
    )
    (net (code "39") (name "LEDRGB-BLU{slash}PTE25") (class "Default")
      (node (ref "R37") (pin "2") (pinfunction "2_2") (pintype "passive"))
      (node (ref "U2") (pin "60") (pinfunction "PTD3_60") (pintype "bidirectional"))
    )
    (net (code "40") (name "LEDRGB-GRN{slash}PTD7") (class "Default")
      (node (ref "R36") (pin "2") (pinfunction "2_2") (pintype "passive"))
      (node (ref "U2") (pin "64") (pinfunction "PTD7_64") (pintype "bidirectional"))
    )
    (net (code "41") (name "LEDRGB-RED{slash}PTD1") (class "Default")
      (node (ref "R43") (pin "2") (pinfunction "2_2") (pintype "passive"))
      (node (ref "U2") (pin "58") (pinfunction "PTD1_58") (pintype "bidirectional"))
    )
    (net (code "42") (name "LOA") (class "Default")
      (node (ref "R8") (pin "1") (pinfunction "1_1") (pintype "passive"))
      (node (ref "U$1") (pin "17") (pinfunction "LO1_17") (pintype "output"))
    )
    (net (code "43") (name "LOB") (class "Default")
      (node (ref "R10") (pin "1") (pinfunction "1_1") (pintype "passive"))
      (node (ref "U$1") (pin "13") (pinfunction "LO2_13") (pintype "output"))
    )
    (net (code "44") (name "LOC") (class "Default")
      (node (ref "R12") (pin "1") (pinfunction "1_1") (pintype "passive"))
      (node (ref "U$1") (pin "7") (pinfunction "LO3_7") (pintype "output"))
    )
    (net (code "45") (name "Net-(CA1-RA1)") (class "Default")
      (node (ref "CA1") (pin "PA1") (pinfunction "RA1_PA1") (pintype "passive"))
      (node (ref "RN2") (pin "8") (pinfunction "8_8") (pintype "passive"))
      (node (ref "RN3") (pin "4") (pinfunction "4_4") (pintype "passive"))
    )
    (net (code "46") (name "Net-(CA1-RB1)") (class "Default")
      (node (ref "CA1") (pin "PB1") (pinfunction "RB1_PB1") (pintype "passive"))
      (node (ref "RN2") (pin "7") (pinfunction "7_7") (pintype "passive"))
      (node (ref "RN3") (pin "3") (pinfunction "3_3") (pintype "passive"))
    )
    (net (code "47") (name "Net-(CA1-RC1)") (class "Default")
      (node (ref "CA1") (pin "PC1") (pinfunction "RC1_PC1") (pintype "passive"))
      (node (ref "RN2") (pin "6") (pinfunction "6_6") (pintype "passive"))
      (node (ref "RN3") (pin "2") (pinfunction "2_2") (pintype "passive"))
    )
    (net (code "48") (name "Net-(D1-PadA)") (class "Default")
      (node (ref "D1") (pin "A") (pinfunction "A_A") (pintype "passive"))
      (node (ref "R29") (pin "2") (pinfunction "2_2") (pintype "passive"))
    )
    (net (code "49") (name "Net-(D2-PadA)") (class "Default")
      (node (ref "D2") (pin "A") (pinfunction "A_A") (pintype "passive"))
      (node (ref "R30") (pin "2") (pinfunction "2_2") (pintype "passive"))
    )
    (net (code "50") (name "Net-(D3-PadA)") (class "Default")
      (node (ref "D3") (pin "A") (pinfunction "A_A") (pintype "passive"))
      (node (ref "R31") (pin "2") (pinfunction "2_2") (pintype "passive"))
    )
    (net (code "51") (name "Net-(D4-A)") (class "Default")
      (node (ref "D4") (pin "2") (pinfunction "A_2") (pintype "passive"))
      (node (ref "R42") (pin "2") (pinfunction "2_2") (pintype "passive"))
    )
    (net (code "52") (name "Net-(D4-CBLUE)") (class "Default")
      (node (ref "D4") (pin "3") (pinfunction "CBLUE_3") (pintype "passive"))
      (node (ref "R37") (pin "1") (pinfunction "1_1") (pintype "passive"))
    )
    (net (code "53") (name "Net-(D4-CGREEN)") (class "Default")
      (node (ref "D4") (pin "4") (pinfunction "CGREEN_4") (pintype "passive"))
      (node (ref "R36") (pin "1") (pinfunction "1_1") (pintype "passive"))
    )
    (net (code "54") (name "Net-(D4-CRED)") (class "Default")
      (node (ref "D4") (pin "1") (pinfunction "CRED_1") (pintype "passive"))
      (node (ref "R43") (pin "1") (pinfunction "1_1") (pintype "passive"))
    )
    (net (code "55") (name "Net-(R1-Pad2)") (class "Default")
      (node (ref "R1") (pin "2") (pinfunction "2_2") (pintype "passive"))
      (node (ref "R13") (pin "1") (pinfunction "1_1") (pintype "passive"))
      (node (ref "U9") (pin "1") (pinfunction "S_1") (pintype "passive"))
      (node (ref "U9") (pin "2") (pinfunction "S_2") (pintype "passive"))
      (node (ref "U9") (pin "3") (pinfunction "S_3") (pintype "passive"))
    )
    (net (code "56") (name "Net-(R4-Pad2)") (class "Default")
      (node (ref "R4") (pin "2") (pinfunction "2_2") (pintype "passive"))
      (node (ref "R6") (pin "1") (pinfunction "1_1") (pintype "passive"))
      (node (ref "U13") (pin "1") (pinfunction "S_1") (pintype "passive"))
      (node (ref "U13") (pin "2") (pinfunction "S_2") (pintype "passive"))
      (node (ref "U13") (pin "3") (pinfunction "S_3") (pintype "passive"))
    )
    (net (code "57") (name "Net-(R17-Pad1)") (class "Default")
      (node (ref "R17") (pin "1") (pinfunction "1_1") (pintype "passive"))
      (node (ref "R2") (pin "2") (pinfunction "2_2") (pintype "passive"))
      (node (ref "U11") (pin "1") (pinfunction "S_1") (pintype "passive"))
      (node (ref "U11") (pin "2") (pinfunction "S_2") (pintype "passive"))
      (node (ref "U11") (pin "3") (pinfunction "S_3") (pintype "passive"))
    )
    (net (code "58") (name "Net-(U$1-VB1)") (class "Default")
      (node (ref "C1") (pin "1") (pinfunction "1_1") (pintype "passive"))
      (node (ref "D3") (pin "C") (pinfunction "C_C") (pintype "passive"))
      (node (ref "U$1") (pin "20") (pinfunction "VB1_20") (pintype "power_in"))
    )
    (net (code "59") (name "Net-(U$1-VB2)") (class "Default")
      (node (ref "C20") (pin "1") (pinfunction "1_1") (pintype "passive"))
      (node (ref "D2") (pin "C") (pinfunction "C_C") (pintype "passive"))
      (node (ref "U$1") (pin "16") (pinfunction "VB2_16") (pintype "power_in"))
    )
    (net (code "60") (name "Net-(U$1-VB3)") (class "Default")
      (node (ref "C22") (pin "1") (pinfunction "1_1") (pintype "passive"))
      (node (ref "D1") (pin "C") (pinfunction "C_C") (pintype "passive"))
      (node (ref "U$1") (pin "10") (pinfunction "VB3_10") (pintype "power_in"))
    )
    (net (code "61") (name "Net-(U$3--IN2)") (class "Default")
      (node (ref "U$3") (pin "6") (pinfunction "-IN2_6") (pintype "input"))
      (node (ref "U$3") (pin "7") (pinfunction "OUT2_7") (pintype "output"))
    )
    (net (code "62") (name "Net-(U$5-+IN1)") (class "Default")
      (node (ref "C10") (pin "1") (pinfunction "1_1") (pintype "passive"))
      (node (ref "R27") (pin "2") (pinfunction "2_2") (pintype "passive"))
      (node (ref "R28") (pin "1") (pinfunction "1_1") (pintype "passive"))
      (node (ref "U$5") (pin "3") (pinfunction "+IN1_3") (pintype "input"))
    )
    (net (code "63") (name "Net-(U1-I3)") (class "Default")
      (node (ref "U1") (pin "6") (pinfunction "~{O2}_6") (pintype "output"))
      (node (ref "U1") (pin "9") (pinfunction "I3_9") (pintype "input"))
    )
    (net (code "64") (name "Net-(U1-I4)") (class "Default")
      (node (ref "U1") (pin "11") (pinfunction "I4_11") (pintype "input"))
      (node (ref "U1") (pin "4") (pinfunction "~{O1}_4") (pintype "output"))
    )
    (net (code "65") (name "Net-(U1-I5)") (class "Default")
      (node (ref "U1") (pin "13") (pinfunction "I5_13") (pintype "input"))
      (node (ref "U1") (pin "2") (pinfunction "~{O0}_2") (pintype "output"))
    )
    (net (code "66") (name "Net-(U2-VDDA)") (class "Default")
      (node (ref "SH3") (pin "2") (pinfunction "2_2") (pintype "passive"))
      (node (ref "U2") (pin "13") (pinfunction "VDDA_13") (pintype "power_in"))
      (node (ref "U2") (pin "14") (pinfunction "VREFH_14") (pintype "power_in"))
    )
    (net (code "67") (name "Net-(U2-VREFL)") (class "Default")
      (node (ref "SH2") (pin "2") (pinfunction "2_2") (pintype "passive"))
      (node (ref "U2") (pin "15") (pinfunction "VREFL_15") (pintype "power_in"))
      (node (ref "U2") (pin "16") (pinfunction "VSSA_16") (pintype "power_in"))
    )
    (net (code "68") (name "Net-(U8-G)") (class "Default")
      (node (ref "R3") (pin "2") (pinfunction "2_2") (pintype "passive"))
      (node (ref "U8") (pin "4") (pinfunction "G_4") (pintype "input"))
    )
    (net (code "69") (name "Net-(U9-G)") (class "Default")
      (node (ref "R8") (pin "2") (pinfunction "2_2") (pintype "passive"))
      (node (ref "U9") (pin "4") (pinfunction "G_4") (pintype "input"))
    )
    (net (code "70") (name "Net-(U10-G)") (class "Default")
      (node (ref "R9") (pin "2") (pinfunction "2_2") (pintype "passive"))
      (node (ref "U10") (pin "4") (pinfunction "G_4") (pintype "input"))
    )
    (net (code "71") (name "Net-(U11-G)") (class "Default")
      (node (ref "R10") (pin "2") (pinfunction "2_2") (pintype "passive"))
      (node (ref "U11") (pin "4") (pinfunction "G_4") (pintype "input"))
    )
    (net (code "72") (name "Net-(U12-G)") (class "Default")
      (node (ref "R11") (pin "2") (pinfunction "2_2") (pintype "passive"))
      (node (ref "U12") (pin "4") (pinfunction "G_4") (pintype "input"))
    )
    (net (code "73") (name "Net-(U13-G)") (class "Default")
      (node (ref "R12") (pin "2") (pinfunction "2_2") (pintype "passive"))
      (node (ref "U13") (pin "4") (pinfunction "G_4") (pintype "input"))
    )
    (net (code "74") (name "PH_A") (class "Default")
      (node (ref "C1") (pin "2") (pinfunction "2_2") (pintype "passive"))
      (node (ref "P1") (pin "P$1") (pinfunction "PAD_P$1") (pintype "passive"))
      (node (ref "U$1") (pin "18") (pinfunction "VS1_18") (pintype "power_in"))
      (node (ref "U8") (pin "1") (pinfunction "S_1") (pintype "passive"))
      (node (ref "U8") (pin "2") (pinfunction "S_2") (pintype "passive"))
      (node (ref "U8") (pin "3") (pinfunction "S_3") (pintype "passive"))
      (node (ref "U9") (pin "5") (pinfunction "D_5") (pintype "open_collector"))
    )
    (net (code "75") (name "PH_B") (class "Default")
      (node (ref "C20") (pin "2") (pinfunction "2_2") (pintype "passive"))
      (node (ref "P2") (pin "P$1") (pinfunction "PAD_P$1") (pintype "passive"))
      (node (ref "U$1") (pin "14") (pinfunction "VS2_14") (pintype "power_in"))
      (node (ref "U10") (pin "1") (pinfunction "S_1") (pintype "passive"))
      (node (ref "U10") (pin "2") (pinfunction "S_2") (pintype "passive"))
      (node (ref "U10") (pin "3") (pinfunction "S_3") (pintype "passive"))
      (node (ref "U11") (pin "5") (pinfunction "D_5") (pintype "open_collector"))
    )
    (net (code "76") (name "PH_C") (class "Default")
      (node (ref "C22") (pin "2") (pinfunction "2_2") (pintype "passive"))
      (node (ref "P3") (pin "P$1") (pinfunction "PAD_P$1") (pintype "passive"))
      (node (ref "U$1") (pin "8") (pinfunction "VS3_8") (pintype "power_in"))
      (node (ref "U12") (pin "1") (pinfunction "S_1") (pintype "passive"))
      (node (ref "U12") (pin "2") (pinfunction "S_2") (pintype "passive"))
      (node (ref "U12") (pin "3") (pinfunction "S_3") (pintype "passive"))
      (node (ref "U13") (pin "5") (pinfunction "D_5") (pintype "open_collector"))
    )
    (net (code "77") (name "PWM_AB") (class "Default")
      (node (ref "U$1") (pin "2") (pinfunction "LIN1_2") (pintype "input"))
      (node (ref "U2") (pin "45") (pinfunction "PTC2_45") (pintype "bidirectional"))
    )
    (net (code "78") (name "PWM_AT") (class "Default")
      (node (ref "U$1") (pin "1") (pinfunction "HIN1_1") (pintype "input"))
      (node (ref "U2") (pin "44") (pinfunction "PTC1/LLWU_P6_44") (pintype "bidirectional"))
    )
    (net (code "79") (name "PWM_BB") (class "Default")
      (node (ref "U$1") (pin "4") (pinfunction "LIN2_4") (pintype "input"))
      (node (ref "U2") (pin "49") (pinfunction "PTC4/LLWU_P8_49") (pintype "bidirectional"))
    )
    (net (code "80") (name "PWM_BT") (class "Default")
      (node (ref "U$1") (pin "3") (pinfunction "HIN2_3") (pintype "input"))
      (node (ref "U2") (pin "50") (pinfunction "PTC5/LLWU_P9_50") (pintype "bidirectional"))
    )
    (net (code "81") (name "PWM_CB") (class "Default")
      (node (ref "U$1") (pin "6") (pinfunction "LIN3_6") (pintype "input"))
      (node (ref "U2") (pin "62") (pinfunction "PTD5_62") (pintype "bidirectional"))
    )
    (net (code "82") (name "PWM_CT") (class "Default")
      (node (ref "U$1") (pin "5") (pinfunction "HIN3_5") (pintype "input"))
      (node (ref "U2") (pin "61") (pinfunction "PTD4/LLWU_P14_61") (pintype "bidirectional"))
    )
    (net (code "83") (name "RESET_B") (class "Default")
      (node (ref "H1") (pin "10") (pinfunction "10_10") (pintype "passive"))
      (node (ref "U2") (pin "34") (pinfunction "RESET_B_34") (pintype "passive"))
    )
    (net (code "84") (name "STB") (class "Default")
      (node (ref "U15") (pin "8") (pinfunction "STB_8") (pintype "input"))
      (node (ref "U2") (pin "27") (pinfunction "PTA5_27") (pintype "bidirectional"))
    )
    (net (code "85") (name "SWD_CLK") (class "Default")
      (node (ref "H1") (pin "4") (pinfunction "4_4") (pintype "passive"))
      (node (ref "U2") (pin "22") (pinfunction "PTA0_22") (pintype "bidirectional"))
    )
    (net (code "86") (name "SWD_DIO") (class "Default")
      (node (ref "H1") (pin "2") (pinfunction "2_2") (pintype "passive"))
      (node (ref "R39") (pin "1") (pinfunction "1_1") (pintype "passive"))
      (node (ref "U2") (pin "25") (pinfunction "PTA3_25") (pintype "bidirectional"))
    )
    (net (code "87") (name "TRACE_SWO") (class "Default")
      (node (ref "H1") (pin "6") (pinfunction "6_6") (pintype "passive"))
      (node (ref "U2") (pin "24") (pinfunction "PTA2_24") (pintype "bidirectional"))
    )
    (net (code "88") (name "VOLT_DCB{slash}ADC0_SE13") (class "Default")
      (node (ref "C24") (pin "1") (pinfunction "1_1") (pintype "passive"))
      (node (ref "R34") (pin "2") (pinfunction "2_2") (pintype "passive"))
      (node (ref "R35") (pin "1") (pinfunction "1_1") (pintype "passive"))
      (node (ref "U2") (pin "38") (pinfunction "PTB3_38") (pintype "bidirectional"))
    )
    (net (code "89") (name "XTAL0") (class "Default")
      (node (ref "C31") (pin "1") (pinfunction "1_1") (pintype "passive"))
      (node (ref "U2") (pin "33") (pinfunction "PTA19_33") (pintype "bidirectional"))
      (node (ref "Y1") (pin "3") (pinfunction "2_3") (pintype "passive"))
    )
    (net (code "90") (name "unconnected-(CA1-RD1-PadPD1)") (class "Default")
      (node (ref "CA1") (pin "PD1") (pinfunction "RD1_PD1") (pintype "passive"))
    )
    (net (code "91") (name "unconnected-(CA1-RD2-PadPD2)") (class "Default")
      (node (ref "CA1") (pin "PD2") (pinfunction "RD2_PD2") (pintype "passive"))
    )
    (net (code "92") (name "unconnected-(H1-Pad7)") (class "Default")
      (node (ref "H1") (pin "7") (pinfunction "7_7") (pintype "passive"))
    )
    (net (code "93") (name "unconnected-(H1-Pad8)") (class "Default")
      (node (ref "H1") (pin "8") (pinfunction "8_8") (pintype "passive"))
    )
    (net (code "94") (name "unconnected-(H1-Pad9)") (class "Default")
      (node (ref "H1") (pin "9") (pinfunction "9_9") (pintype "passive"))
    )
    (net (code "95") (name "unconnected-(J1A-S-Pad10)") (class "Default")
      (node (ref "J1") (pin "10") (pinfunction "S_10") (pintype "passive"))
    )
    (net (code "96") (name "unconnected-(J1B-S-Pad3)") (class "Default")
      (node (ref "J1") (pin "3") (pinfunction "S_3") (pintype "passive"))
    )
    (net (code "97") (name "unconnected-(J1C-S-Pad5)") (class "Default")
      (node (ref "J1") (pin "5") (pinfunction "S_5") (pintype "passive"))
    )
    (net (code "98") (name "unconnected-(J1D-S-Pad9)") (class "Default")
      (node (ref "J1") (pin "9") (pinfunction "S_9") (pintype "passive"))
    )
    (net (code "99") (name "unconnected-(J1E-S-Pad4)") (class "Default")
      (node (ref "J1") (pin "4") (pinfunction "S_4") (pintype "passive"))
    )
    (net (code "100") (name "unconnected-(J1F-S-Pad8)") (class "Default")
      (node (ref "J1") (pin "8") (pinfunction "S_8") (pintype "passive"))
    )
    (net (code "101") (name "unconnected-(J1G-S-Pad6)") (class "Default")
      (node (ref "J1") (pin "6") (pinfunction "S_6") (pintype "passive"))
    )
    (net (code "102") (name "unconnected-(J1H-S-Pad2)") (class "Default")
      (node (ref "J1") (pin "2") (pinfunction "S_2") (pintype "passive"))
    )
    (net (code "103") (name "unconnected-(J1I-S-Pad1)") (class "Default")
      (node (ref "J1") (pin "1") (pinfunction "S_1") (pintype "passive"))
    )
    (net (code "104") (name "unconnected-(P15A-S-Pad1)") (class "Default")
      (node (ref "P15") (pin "1") (pinfunction "S_1") (pintype "passive"))
    )
    (net (code "105") (name "unconnected-(P15B-S-Pad2)") (class "Default")
      (node (ref "P15") (pin "2") (pinfunction "S_2") (pintype "passive"))
    )
    (net (code "106") (name "unconnected-(P15C-S-Pad3)") (class "Default")
      (node (ref "P15") (pin "3") (pinfunction "S_3") (pintype "passive"))
    )
    (net (code "107") (name "unconnected-(P15D-S-Pad4)") (class "Default")
      (node (ref "P15") (pin "4") (pinfunction "S_4") (pintype "passive"))
    )
    (net (code "108") (name "unconnected-(P15E-S-Pad5)") (class "Default")
      (node (ref "P15") (pin "5") (pinfunction "S_5") (pintype "passive"))
    )
    (net (code "109") (name "unconnected-(P15F-S-Pad6)") (class "Default")
      (node (ref "P15") (pin "6") (pinfunction "S_6") (pintype "passive"))
    )
    (net (code "110") (name "unconnected-(R40-Pad1)") (class "Default")
      (node (ref "R40") (pin "1") (pinfunction "1_1") (pintype "passive"))
    )
    (net (code "111") (name "unconnected-(R40-Pad2)") (class "Default")
      (node (ref "R40") (pin "2") (pinfunction "2_2") (pintype "passive"))
    )
    (net (code "112") (name "unconnected-(RN1-Pad4)") (class "Default")
      (node (ref "RN1") (pin "4") (pinfunction "4_4") (pintype "passive"))
    )
    (net (code "113") (name "unconnected-(RN1-Pad5)") (class "Default")
      (node (ref "RN1") (pin "5") (pinfunction "5_5") (pintype "passive"))
    )
    (net (code "114") (name "unconnected-(RN2-Pad4)") (class "Default")
      (node (ref "RN2") (pin "4") (pinfunction "4_4") (pintype "passive"))
    )
    (net (code "115") (name "unconnected-(RN2-Pad5)") (class "Default")
      (node (ref "RN2") (pin "5") (pinfunction "5_5") (pintype "passive"))
    )
    (net (code "116") (name "unconnected-(RN3-Pad1)") (class "Default")
      (node (ref "RN3") (pin "1") (pinfunction "1_1") (pintype "passive"))
    )
    (net (code "117") (name "unconnected-(RN3-Pad8)") (class "Default")
      (node (ref "RN3") (pin "8") (pinfunction "8_8") (pintype "passive"))
    )
    (net (code "118") (name "unconnected-(U$15A-S-Pad4)") (class "Default")
      (node (ref "U$15") (pin "4") (pinfunction "S_4") (pintype "passive"))
    )
    (net (code "119") (name "unconnected-(U$15B-S-Pad2)") (class "Default")
      (node (ref "U$15") (pin "2") (pinfunction "S_2") (pintype "passive"))
    )
    (net (code "120") (name "unconnected-(U$15C-S-Pad3)") (class "Default")
      (node (ref "U$15") (pin "3") (pinfunction "S_3") (pintype "passive"))
    )
    (net (code "121") (name "unconnected-(U$15D-S-Pad1)") (class "Default")
      (node (ref "U$15") (pin "1") (pinfunction "S_1") (pintype "passive"))
    )
    (net (code "122") (name "unconnected-(U2-ADC0_DM0{slash}ADC1_DM3-Pad10)") (class "Default")
      (node (ref "U2") (pin "10") (pinfunction "ADC0_DM0/ADC1_DM3_10") (pintype "bidirectional"))
    )
    (net (code "123") (name "unconnected-(U2-ADC0_DP0{slash}ADC1_DP3-Pad9)") (class "Default")
      (node (ref "U2") (pin "9") (pinfunction "ADC0_DP0/ADC1_DP3_9") (pintype "bidirectional"))
    )
    (net (code "124") (name "unconnected-(U2-ADC1_DM0{slash}ADC0_DM3-Pad12)") (class "Default")
      (node (ref "U2") (pin "12") (pinfunction "ADC1_DM0/ADC0_DM3_12") (pintype "bidirectional"))
    )
    (net (code "125") (name "unconnected-(U2-ADC1_DP0{slash}ADC0_DP3-Pad11)") (class "Default")
      (node (ref "U2") (pin "11") (pinfunction "ADC1_DP0/ADC0_DP3_11") (pintype "bidirectional"))
    )
    (net (code "126") (name "unconnected-(U2-DAC0_OUT{slash}CMP1_IN3{slash}ADC0_SE23-Pad18)") (class "Default")
      (node (ref "U2") (pin "18") (pinfunction "DAC0_OUT/CMP1_IN3/ADC0_SE23_18") (pintype "bidirectional"))
    )
    (net (code "127") (name "unconnected-(U2-DAC1_OUT{slash}CMP0_IN4{slash}ADC1_SE23-Pad19)") (class "Default")
      (node (ref "U2") (pin "19") (pinfunction "DAC1_OUT/CMP0_IN4/ADC1_SE23_19") (pintype "bidirectional"))
    )
    (net (code "128") (name "unconnected-(U2-PTA1-Pad23)") (class "Default")
      (node (ref "U2") (pin "23") (pinfunction "PTA1_23") (pintype "bidirectional"))
    )
    (net (code "129") (name "unconnected-(U2-PTA4{slash}LLWU_P3-Pad26)") (class "Default")
      (node (ref "U2") (pin "26") (pinfunction "PTA4/LLWU_P3_26") (pintype "bidirectional"))
    )
    (net (code "130") (name "unconnected-(U2-PTA12-Pad28)") (class "Default")
      (node (ref "U2") (pin "28") (pinfunction "PTA12_28") (pintype "bidirectional"))
    )
    (net (code "131") (name "unconnected-(U2-PTB0{slash}LLWU_P5-Pad35)") (class "Default")
      (node (ref "U2") (pin "35") (pinfunction "PTB0/LLWU_P5_35") (pintype "bidirectional"))
    )
    (net (code "132") (name "unconnected-(U2-PTB1-Pad36)") (class "Default")
      (node (ref "U2") (pin "36") (pinfunction "PTB1_36") (pintype "bidirectional"))
    )
    (net (code "133") (name "unconnected-(U2-PTB2-Pad37)") (class "Default")
      (node (ref "U2") (pin "37") (pinfunction "PTB2_37") (pintype "bidirectional"))
    )
    (net (code "134") (name "unconnected-(U2-PTB16-Pad39)") (class "Default")
      (node (ref "U2") (pin "39") (pinfunction "PTB16_39") (pintype "bidirectional"))
    )
    (net (code "135") (name "unconnected-(U2-PTB17-Pad40)") (class "Default")
      (node (ref "U2") (pin "40") (pinfunction "PTB17_40") (pintype "bidirectional"))
    )
    (net (code "136") (name "unconnected-(U2-PTC0-Pad43)") (class "Default")
      (node (ref "U2") (pin "43") (pinfunction "PTC0_43") (pintype "bidirectional"))
    )
    (net (code "137") (name "unconnected-(U2-PTC3{slash}LLWU_P7-Pad46)") (class "Default")
      (node (ref "U2") (pin "46") (pinfunction "PTC3/LLWU_P7_46") (pintype "bidirectional"))
    )
    (net (code "138") (name "unconnected-(U2-PTC6{slash}LLWU_P10-Pad51)") (class "Default")
      (node (ref "U2") (pin "51") (pinfunction "PTC6/LLWU_P10_51") (pintype "bidirectional"))
    )
    (net (code "139") (name "unconnected-(U2-PTC7-Pad52)") (class "Default")
      (node (ref "U2") (pin "52") (pinfunction "PTC7_52") (pintype "bidirectional"))
    )
    (net (code "140") (name "unconnected-(U2-PTC8-Pad53)") (class "Default")
      (node (ref "U2") (pin "53") (pinfunction "PTC8_53") (pintype "bidirectional"))
    )
    (net (code "141") (name "unconnected-(U2-PTC9-Pad54)") (class "Default")
      (node (ref "U2") (pin "54") (pinfunction "PTC9_54") (pintype "bidirectional"))
    )
    (net (code "142") (name "unconnected-(U2-PTC10-Pad55)") (class "Default")
      (node (ref "U2") (pin "55") (pinfunction "PTC10_55") (pintype "bidirectional"))
    )
    (net (code "143") (name "unconnected-(U2-PTC11{slash}LLWU_P11-Pad56)") (class "Default")
      (node (ref "U2") (pin "56") (pinfunction "PTC11/LLWU_P11_56") (pintype "bidirectional"))
    )
    (net (code "144") (name "unconnected-(U2-PTD0{slash}LLWU_P12-Pad57)") (class "Default")
      (node (ref "U2") (pin "57") (pinfunction "PTD0/LLWU_P12_57") (pintype "bidirectional"))
    )
    (net (code "145") (name "unconnected-(U2-PTD2{slash}LLWU_P13-Pad59)") (class "Default")
      (node (ref "U2") (pin "59") (pinfunction "PTD2/LLWU_P13_59") (pintype "bidirectional"))
    )
    (net (code "146") (name "unconnected-(U2-PTD6{slash}LLWU_P15-Pad63)") (class "Default")
      (node (ref "U2") (pin "63") (pinfunction "PTD6/LLWU_P15_63") (pintype "bidirectional"))
    )
    (net (code "147") (name "unconnected-(U2-PTE0{slash}CLKOUT32K-Pad1)") (class "Default")
      (node (ref "U2") (pin "1") (pinfunction "PTE0/CLKOUT32K_1") (pintype "bidirectional"))
    )
    (net (code "148") (name "unconnected-(U2-PTE1{slash}LLWU_P0-Pad2)") (class "Default")
      (node (ref "U2") (pin "2") (pinfunction "PTE1/LLWU_P0_2") (pintype "bidirectional"))
    )
    (net (code "149") (name "unconnected-(U2-PTE16-Pad5)") (class "Default")
      (node (ref "U2") (pin "5") (pinfunction "PTE16_5") (pintype "bidirectional"))
    )
    (net (code "150") (name "unconnected-(U2-PTE17-Pad6)") (class "Default")
      (node (ref "U2") (pin "6") (pinfunction "PTE17_6") (pintype "bidirectional"))
    )
    (net (code "151") (name "unconnected-(U2-VREF_OUT{slash}CMP1_IN5{slash}CMP0_IN5{slash}ADC1_SE18-Pad17)") (class "Default")
      (node (ref "U2") (pin "17") (pinfunction "VREF_OUT/CMP1_IN5/CMP0_IN5/ADC1_SE18_17") (pintype "bidirectional"))
    )
  )
)
